# TMC2160.net
KiCad netlist of a schematic drawn in Altium Designer
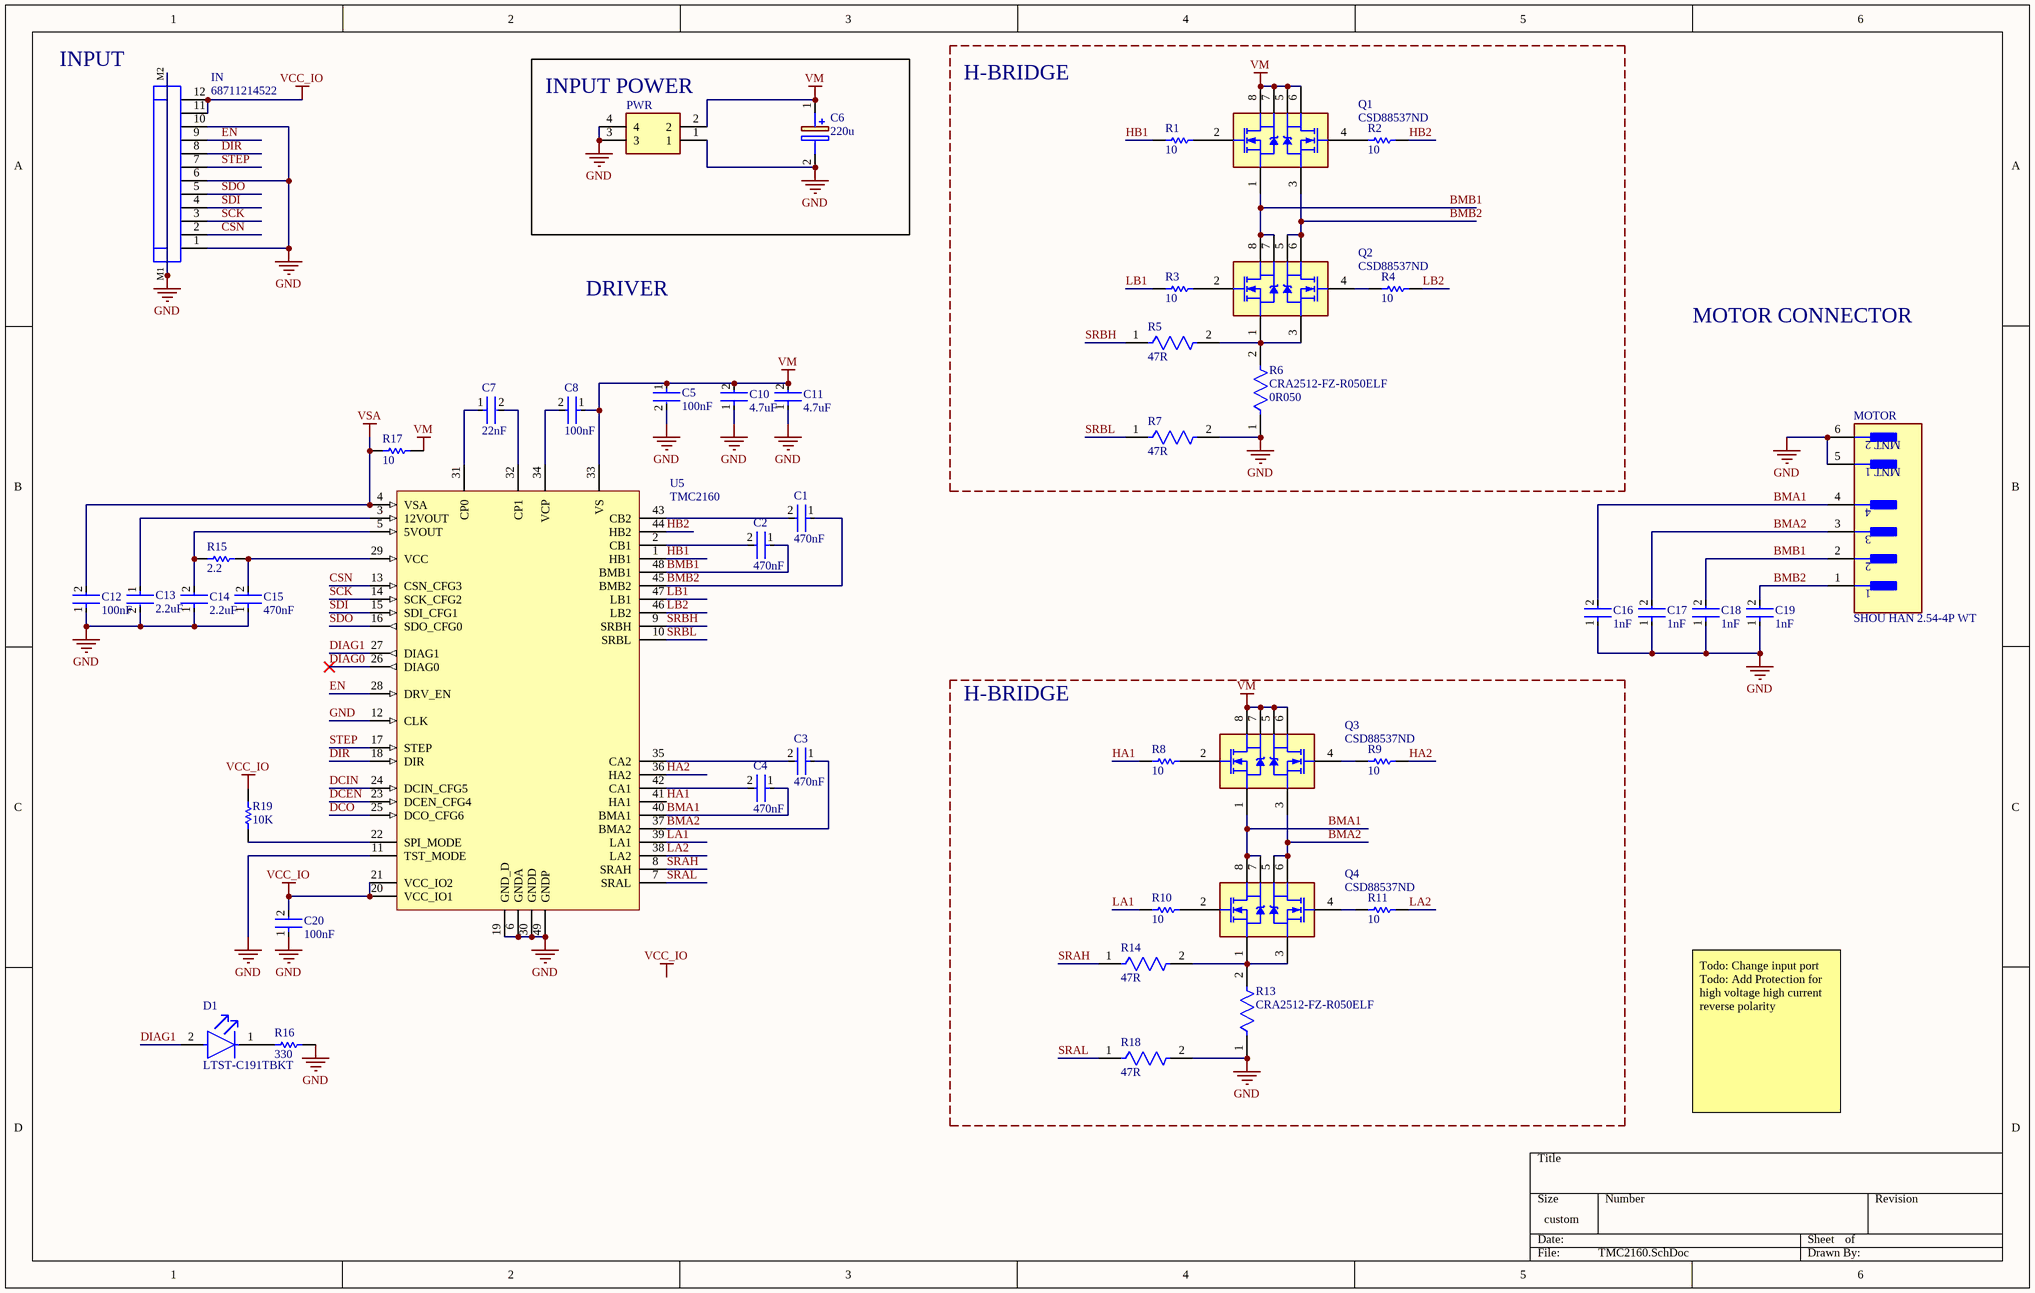
[diagram p0: TMC2160.SchDoc]

(export (version "E")
  (design (tool "Eeschema 10.0.6"))
  (components
    (comp (ref "C1")
      (value "470nF")
      (footprint "FP-C1005-050-0_05-IPC_B")
      (description "Multilayer Ceramic Capacitors 470nF ±10% 35V X5R SMD 0402")
      (fields (field (name "TOLERANCE") "10%") (field (name "Comment") "C1005X5R1V474K050BC"))
      (libsource (lib "Altium Content Vault") (part "b4654b650e69147ec39a6b967a45e02"))
    )
    (comp (ref "C2")
      (value "470nF")
      (footprint "FP-C1005-050-0_05-IPC_B")
      (description "Multilayer Ceramic Capacitors 470nF ±10% 35V X5R SMD 0402")
      (fields (field (name "TOLERANCE") "10%") (field (name "Comment") "C1005X5R1V474K050BC"))
      (libsource (lib "Altium Content Vault") (part "b4654b650e69147ec39a6b967a45e02"))
    )
    (comp (ref "C3")
      (value "470nF")
      (footprint "FP-C1005-050-0_05-IPC_B")
      (description "Multilayer Ceramic Capacitors 470nF ±10% 35V X5R SMD 0402")
      (fields (field (name "TOLERANCE") "10%") (field (name "Comment") "C1005X5R1V474K050BC"))
      (libsource (lib "Altium Content Vault") (part "b4654b650e69147ec39a6b967a45e02"))
    )
    (comp (ref "C4")
      (value "470nF")
      (footprint "FP-C1005-050-0_05-IPC_B")
      (description "Multilayer Ceramic Capacitors 470nF ±10% 35V X5R SMD 0402")
      (fields (field (name "TOLERANCE") "10%") (field (name "Comment") "C1005X5R1V474K050BC"))
      (libsource (lib "Altium Content Vault") (part "b4654b650e69147ec39a6b967a45e02"))
    )
    (comp (ref "C5")
      (value "100nF")
      (footprint "FP-C1005-050-0_05-IPC_C")
      (description "Multilayer Ceramic Capacitors 100nF ±10% 50V X7R SMD 0402")
      (fields (field (name "VOLTAGE") "50V") (field (name "TOLERANCE") "10%"))
      (libsource (lib "Altium Content Vault") (part "b4654b650e69147ec39a6b967a45e02"))
    )
    (comp (ref "C6")
      (value "220u")
      (footprint "SamacSys:CAPAE1030X1050N")
      (description "Capacitor Polarised")
      (fields (field (name "MANUFACTURER_PART_NUMBER") "VZH221M1HTR-1010L"))
      (libsource (lib "SamacSys") (part "VZH221M1HTR-1010L"))
    )
    (comp (ref "C7")
      (value "22nF")
      (footprint "FP-C1005-050-0_05-IPC_C")
      (description "Multilayer Ceramic Capacitors 22nF ±10% 50V X7R SMD 0402")
      (fields (field (name "TOLERANCE") "10%") (field (name "Comment") "C1005X7R1H223K050BB"))
      (libsource (lib "Altium Content Vault") (part "b4654b650e69147ec39a6b967a45e02"))
    )
    (comp (ref "C8")
      (value "100nF")
      (footprint "FP-C1005-050-0_05-IPC_C")
      (description "Multilayer Ceramic Capacitors 100nF ±10% 50V X7R SMD 0402")
      (fields (field (name "VOLTAGE") "50V") (field (name "TOLERANCE") "10%"))
      (libsource (lib "Altium Content Vault") (part "b4654b650e69147ec39a6b967a45e02"))
    )
    (comp (ref "C10")
      (value "4.7uF")
      (footprint "FP-GRM21B-0_15-IPC_B")
      (description "Chip Multilayer Ceramic Capacitors for General Purpose, 0805, 4.7uF, X5R, 15%, 10%, 50V")
      (fields (field (name "TOLERANCE") "10%") (field (name "Comment") "GRM21BR61H475KE51L"))
      (libsource (lib "Altium Content Vault") (part "b4654b650e69147ec39a6b967a45e02"))
    )
    (comp (ref "C11")
      (value "4.7uF")
      (footprint "FP-GRM21B-0_15-IPC_B")
      (description "Chip Multilayer Ceramic Capacitors for General Purpose, 0805, 4.7uF, X5R, 15%, 10%, 50V")
      (fields (field (name "TOLERANCE") "10%") (field (name "Comment") "GRM21BR61H475KE51L"))
      (libsource (lib "Altium Content Vault") (part "b4654b650e69147ec39a6b967a45e02"))
    )
    (comp (ref "C12")
      (value "100nF")
      (footprint "FP-C1005-050-0_05-IPC_C")
      (description "Multilayer Ceramic Capacitors 100nF ±10% 50V X7R SMD 0402")
      (fields (field (name "VOLTAGE") "50V") (field (name "TOLERANCE") "10%"))
      (libsource (lib "Altium Content Vault") (part "b4654b650e69147ec39a6b967a45e02"))
    )
    (comp (ref "C13")
      (value "2.2uF")
      (footprint "FP-C1005-050-0_15-IPC_C")
      (description "CAP CER 2.2UF 35V X5R 0402")
      (fields (field (name "TOLERANCE") "10%") (field (name "Comment") "C1005X5R1V225K050BC"))
      (libsource (lib "Altium Content Vault") (part "11868f565c42a9108669ba33697ecf6"))
    )
    (comp (ref "C14")
      (value "2.2uF")
      (footprint "FP-C1005-050-0_15-IPC_A")
      (description "CAP CER 2.2UF 35V X5R 0402")
      (fields (field (name "TOLERANCE") "10%") (field (name "Comment") "C1005X5R1V225K050BC"))
      (libsource (lib "Altium Content Vault") (part "11868f565c42a9108669ba33697ecf6"))
    )
    (comp (ref "C15")
      (value "470nF")
      (footprint "FP-C1005-050-0_05-IPC_B")
      (description "Multilayer Ceramic Capacitors 470nF ±10% 35V X5R SMD 0402")
      (fields (field (name "TOLERANCE") "10%") (field (name "Comment") "C1005X5R1V474K050BC"))
      (libsource (lib "Altium Content Vault") (part "b4654b650e69147ec39a6b967a45e02"))
    )
    (comp (ref "C16")
      (value "1nF")
      (footprint "FP-C1005-050-0_05-IPC_A")
      (description "Multilayer Ceramic Capacitors 1nF ±10% 50V X7R SMD 0402")
      (fields (field (name "TOLERANCE") "10%") (field (name "VOLTAGE") "50V"))
      (libsource (lib "Altium Content Vault") (part "b4654b650e69147ec39a6b967a45e02"))
    )
    (comp (ref "C17")
      (value "1nF")
      (footprint "FP-C1005-050-0_05-IPC_A")
      (description "Multilayer Ceramic Capacitors 1nF ±10% 50V X7R SMD 0402")
      (fields (field (name "TOLERANCE") "10%") (field (name "VOLTAGE") "50V"))
      (libsource (lib "Altium Content Vault") (part "b4654b650e69147ec39a6b967a45e02"))
    )
    (comp (ref "C18")
      (value "1nF")
      (footprint "FP-C1005-050-0_05-IPC_A")
      (description "Multilayer Ceramic Capacitors 1nF ±10% 50V X7R SMD 0402")
      (fields (field (name "TOLERANCE") "10%") (field (name "VOLTAGE") "50V"))
      (libsource (lib "Altium Content Vault") (part "b4654b650e69147ec39a6b967a45e02"))
    )
    (comp (ref "C19")
      (value "1nF")
      (footprint "FP-C1005-050-0_05-IPC_A")
      (description "Multilayer Ceramic Capacitors 1nF ±10% 50V X7R SMD 0402")
      (fields (field (name "TOLERANCE") "10%") (field (name "VOLTAGE") "50V"))
      (libsource (lib "Altium Content Vault") (part "b4654b650e69147ec39a6b967a45e02"))
    )
    (comp (ref "C20")
      (value "100nF")
      (footprint "FP-C1005-050-0_05-IPC_C")
      (description "Multilayer Ceramic Capacitors 100nF ±10% 50V X7R SMD 0402")
      (fields (field (name "VOLTAGE") "50V") (field (name "TOLERANCE") "10%"))
      (libsource (lib "Altium Content Vault") (part "b4654b650e69147ec39a6b967a45e02"))
    )
    (comp (ref "D1")
      (value "LTST-C191TBKT")
      (footprint "FP-LTST-C191TBKT-MFG")
      (description "LED BLUE CLEAR CHIP SMD")
      (libsource (lib "Altium Content Vault") (part "8706943c75ba83719d021d2fdc84c58"))
    )
    (comp (ref "IN")
      (value "68711214522")
      (footprint "68711214522")
      (libsource (lib "Altium Content Vault") (part "FPC - 12P - 2MP"))
    )
    (comp (ref "MOTOR")
      (value "SHOU HAN 2.54-4P WT")
      (footprint "A2501WF-04A")
      (description "CONN HEADER SMD R/A 4POS 2.5MM")
      (libsource (lib "ParsaLibrary") (part "a9f55b2ccc20dccd0fcbea9c396e26a"))
    )
    (comp (ref "PWR")
      (value "SHOU HAN 2.54-2P WT")
      (footprint "A2501WF-02A")
      (description "Connector")
      (fields
        (field (name "MANUFACTURER_PART_NUMBER") "1778764")
        (field (name "MOUSER PART NUMBER") "651-1778764")
      )
      (libsource (lib "*") (part "1778764"))
    )
    (comp (ref "Q1")
      (value "CSD88537ND")
      (footprint "SamacSys:SOIC127P600X175-8N")
      (description "MOSFET (N-Channel)")
      (fields (field (name "MOUSER PART NUMBER") "595-CSD88537ND"))
      (libsource (lib "SamacSys") (part "CSD88537ND"))
    )
    (comp (ref "Q2")
      (value "CSD88537ND")
      (footprint "SamacSys:SOIC127P600X175-8N")
      (description "MOSFET (N-Channel)")
      (fields (field (name "MOUSER PART NUMBER") "595-CSD88537ND"))
      (libsource (lib "SamacSys") (part "CSD88537ND"))
    )
    (comp (ref "Q3")
      (value "CSD88537ND")
      (footprint "SamacSys:SOIC127P600X175-8N")
      (description "MOSFET (N-Channel)")
      (fields (field (name "MOUSER PART NUMBER") "595-CSD88537ND"))
      (libsource (lib "SamacSys") (part "CSD88537ND"))
    )
    (comp (ref "Q4")
      (value "CSD88537ND")
      (footprint "SamacSys:SOIC127P600X175-8N")
      (description "MOSFET (N-Channel)")
      (fields (field (name "MOUSER PART NUMBER") "595-CSD88537ND"))
      (libsource (lib "SamacSys") (part "CSD88537ND"))
    )
    (comp (ref "R1")
      (value "10")
      (footprint "RESC1005X40X25ML05T10")
      (fields
        (field (name "PART NUMBER") "RC0402FR-07100RL")
        (field (name "MANUFACTURER") "Yageo / Phycomp")
        (field (name "Comment") "RC0402FR-0710RL")
      )
      (libsource (lib "Altium Content Vault") (part "RES"))
    )
    (comp (ref "R2")
      (value "10")
      (footprint "RESC1005X40X25ML05T10")
      (fields
        (field (name "PART NUMBER") "RC0402FR-07100RL")
        (field (name "MANUFACTURER") "Yageo / Phycomp")
        (field (name "Comment") "RC0402FR-0710RL")
      )
      (libsource (lib "Altium Content Vault") (part "RES"))
    )
    (comp (ref "R3")
      (value "10")
      (footprint "RESC1005X40X25ML05T10")
      (fields
        (field (name "PART NUMBER") "RC0402FR-07100RL")
        (field (name "MANUFACTURER") "Yageo / Phycomp")
        (field (name "Comment") "RC0402FR-0710RL")
      )
      (libsource (lib "Altium Content Vault") (part "RES"))
    )
    (comp (ref "R4")
      (value "10")
      (footprint "RESC1005X40X25ML05T10")
      (fields
        (field (name "PART NUMBER") "RC0402FR-07100RL")
        (field (name "MANUFACTURER") "Yageo / Phycomp")
        (field (name "Comment") "RC0402FR-0710RL")
      )
      (libsource (lib "Altium Content Vault") (part "RES"))
    )
    (comp (ref "R5")
      (value "47R")
      (footprint "FP-ERJ2RK-IPC_C")
      (description "RES SMD 47 OHM 1% 1/10W 0402")
      (fields (field (name "TOLERANCE") "1%") (field (name "Comment") "ERJ-2RKF47R0X"))
      (libsource (lib "Altium Content Vault") (part "1029c3af85768c4190bb7ad29bc67b5"))
    )
    (comp (ref "R6")
      (value "CRA2512-FZ-R050ELF")
      (footprint "FP-CRA2512-IPC_A")
      (description "RES 0.05 OHM 1% 3W 2512")
      (fields (field (name "ALTIUM_VALUE") "0R050"))
      (libsource (lib "Altium Content Vault") (part "1029c3af85768c4190bb7ad29bc67b5"))
    )
    (comp (ref "R7")
      (value "47R")
      (footprint "FP-ERJ2RK-IPC_C")
      (description "RES SMD 47 OHM 1% 1/10W 0402")
      (fields (field (name "TOLERANCE") "1%") (field (name "Comment") "ERJ-2RKF47R0X"))
      (libsource (lib "Altium Content Vault") (part "1029c3af85768c4190bb7ad29bc67b5"))
    )
    (comp (ref "R8")
      (value "10")
      (footprint "RESC1005X40X25ML05T10")
      (fields
        (field (name "PART NUMBER") "RC0402FR-07100RL")
        (field (name "MANUFACTURER") "Yageo / Phycomp")
        (field (name "Comment") "RC0402FR-0710RL")
      )
      (libsource (lib "Altium Content Vault") (part "RES"))
    )
    (comp (ref "R9")
      (value "10")
      (footprint "RESC1005X40X25ML05T10")
      (fields
        (field (name "PART NUMBER") "RC0402FR-07100RL")
        (field (name "MANUFACTURER") "Yageo / Phycomp")
        (field (name "Comment") "RC0402FR-0710RL")
      )
      (libsource (lib "Altium Content Vault") (part "RES"))
    )
    (comp (ref "R10")
      (value "10")
      (footprint "RESC1005X40X25ML05T10")
      (fields
        (field (name "PART NUMBER") "RC0402FR-07100RL")
        (field (name "MANUFACTURER") "Yageo / Phycomp")
        (field (name "Comment") "RC0402FR-0710RL")
      )
      (libsource (lib "Altium Content Vault") (part "RES"))
    )
    (comp (ref "R11")
      (value "10")
      (footprint "RESC1005X40X25ML05T10")
      (fields
        (field (name "PART NUMBER") "RC0402FR-07100RL")
        (field (name "MANUFACTURER") "Yageo / Phycomp")
        (field (name "Comment") "RC0402FR-0710RL")
      )
      (libsource (lib "Altium Content Vault") (part "RES"))
    )
    (comp (ref "R13")
      (value "CRA2512-FZ-R050ELF")
      (footprint "FP-CRA2512-IPC_A")
      (description "RES 0.05 OHM 1% 3W 2512")
      (libsource (lib "Altium Content Vault") (part "1029c3af85768c4190bb7ad29bc67b5"))
    )
    (comp (ref "R14")
      (value "47R")
      (footprint "FP-ERJ2RK-IPC_C")
      (description "RES SMD 47 OHM 1% 1/10W 0402")
      (fields (field (name "TOLERANCE") "1%") (field (name "Comment") "ERJ-2RKF47R0X"))
      (libsource (lib "Altium Content Vault") (part "1029c3af85768c4190bb7ad29bc67b5"))
    )
    (comp (ref "R15")
      (value "ERJ-2GEJ2R2X")
      (footprint "RESC1005X40X25ML05T05")
      (fields (field (name "MANUFACTURER") "Panasonic") (field (name "RESISTANCE") "2.2"))
      (libsource (lib "Altium Content Vault") (part "RES"))
    )
    (comp (ref "R16")
      (value "330")
      (footprint "RESC1005X40X25LL05T10")
      (fields (field (name "PART NUMBER") "RC0402FR-07330RL") (field (name "MANUFACTURER") "Yageo / Phycomp"))
      (libsource (lib "Altium Content Vault") (part "RES"))
    )
    (comp (ref "R17")
      (value "10")
      (footprint "RESC1005X40X25ML05T10")
      (fields
        (field (name "PART NUMBER") "RC0402FR-07100RL")
        (field (name "MANUFACTURER") "Yageo / Phycomp")
        (field (name "Comment") "RC0402FR-0710RL")
      )
      (libsource (lib "Altium Content Vault") (part "RES"))
    )
    (comp (ref "R18")
      (value "47R")
      (footprint "FP-ERJ2RK-IPC_C")
      (description "RES SMD 47 OHM 1% 1/10W 0402")
      (fields (field (name "TOLERANCE") "1%") (field (name "Comment") "ERJ-2RKF47R0X"))
      (libsource (lib "Altium Content Vault") (part "1029c3af85768c4190bb7ad29bc67b5"))
    )
    (comp (ref "R19")
      (value "10K")
      (footprint "RESC1005X40X25LL05T10")
      (fields (field (name "PART NUMBER") "RC0402FR-0710KL") (field (name "MANUFACTURER") "Yageo / Phycomp"))
      (libsource (lib "Altium Content Vault") (part "RES"))
    )
    (comp (ref "U5") (value "TMC2160") (footprint "TSQFP-48") (libsource (lib "Schlib2") (part "TMC2160")))
  )
  (nets
    (net (code "1") (name "/BMA1") (class "Default")
      (node (ref "C16") (pin "2") (pinfunction "2_2") (pintype "passive"))
      (node (ref "C4") (pin "1") (pinfunction "1_1") (pintype "passive"))
      (node (ref "MOTOR") (pin "4") (pinfunction "4_4") (pintype "passive"))
      (node (ref "Q3") (pin "1") (pinfunction "S1_1") (pintype "passive"))
      (node (ref "Q4") (pin "7") (pinfunction "D1_1_7") (pintype "passive"))
      (node (ref "Q4") (pin "8") (pinfunction "D1_2_8") (pintype "passive"))
      (node (ref "U5") (pin "40") (pinfunction "BMA1_40") (pintype "passive"))
    )
    (net (code "2") (name "/BMA2") (class "Default")
      (node (ref "C17") (pin "2") (pinfunction "2_2") (pintype "passive"))
      (node (ref "C3") (pin "1") (pinfunction "1_1") (pintype "passive"))
      (node (ref "MOTOR") (pin "3") (pinfunction "3_3") (pintype "passive"))
      (node (ref "Q3") (pin "3") (pinfunction "S2_3") (pintype "passive"))
      (node (ref "Q4") (pin "5") (pinfunction "D2_1_5") (pintype "passive"))
      (node (ref "Q4") (pin "6") (pinfunction "D2_2_6") (pintype "passive"))
      (node (ref "U5") (pin "37") (pinfunction "BMA2_37") (pintype "passive"))
    )
    (net (code "3") (name "/BMB1") (class "Default")
      (node (ref "C18") (pin "2") (pinfunction "2_2") (pintype "passive"))
      (node (ref "C2") (pin "1") (pinfunction "1_1") (pintype "passive"))
      (node (ref "MOTOR") (pin "2") (pinfunction "2_2") (pintype "passive"))
      (node (ref "Q1") (pin "1") (pinfunction "S1_1") (pintype "passive"))
      (node (ref "Q2") (pin "7") (pinfunction "D1_1_7") (pintype "passive"))
      (node (ref "Q2") (pin "8") (pinfunction "D1_2_8") (pintype "passive"))
      (node (ref "U5") (pin "48") (pinfunction "BMB1_48") (pintype "passive"))
    )
    (net (code "4") (name "/BMB2") (class "Default")
      (node (ref "C1") (pin "1") (pinfunction "1_1") (pintype "passive"))
      (node (ref "C19") (pin "2") (pinfunction "2_2") (pintype "passive"))
      (node (ref "MOTOR") (pin "1") (pinfunction "1_1") (pintype "passive"))
      (node (ref "Q1") (pin "3") (pinfunction "S2_3") (pintype "passive"))
      (node (ref "Q2") (pin "5") (pinfunction "D2_1_5") (pintype "passive"))
      (node (ref "Q2") (pin "6") (pinfunction "D2_2_6") (pintype "passive"))
      (node (ref "U5") (pin "45") (pinfunction "BMB2_45") (pintype "passive"))
    )
    (net (code "5") (name "/CSN") (class "Default")
      (node (ref "IN") (pin "2") (pinfunction "2_2") (pintype "passive"))
      (node (ref "U5") (pin "13") (pinfunction "CSN_CFG3_13") (pintype "input"))
    )
    (net (code "6") (name "/DCEN") (class "Default")
      (node (ref "U5") (pin "23") (pinfunction "DCEN_CFG4_23") (pintype "input"))
    )
    (net (code "7") (name "/DCIN") (class "Default")
      (node (ref "U5") (pin "24") (pinfunction "DCIN_CFG5_24") (pintype "input"))
    )
    (net (code "8") (name "/DCO") (class "Default")
      (node (ref "U5") (pin "25") (pinfunction "DCO_CFG6_25") (pintype "input"))
    )
    (net (code "9") (name "/DIAG0") (class "Default")
      (node (ref "U5") (pin "26") (pinfunction "DIAG0_26") (pintype "output+no_connect"))
    )
    (net (code "10") (name "/DIAG1") (class "Default")
      (node (ref "D1") (pin "2") (pinfunction "A_2") (pintype "passive"))
      (node (ref "U5") (pin "27") (pinfunction "DIAG1_27") (pintype "output"))
    )
    (net (code "11") (name "/DIR") (class "Default")
      (node (ref "IN") (pin "8") (pinfunction "8_8") (pintype "passive"))
      (node (ref "U5") (pin "18") (pinfunction "DIR_18") (pintype "input"))
    )
    (net (code "12") (name "/EN") (class "Default")
      (node (ref "IN") (pin "9") (pinfunction "9_9") (pintype "passive"))
      (node (ref "U5") (pin "28") (pinfunction "DRV_EN_28") (pintype "input"))
    )
    (net (code "13") (name "/HA1") (class "Default")
      (node (ref "R8") (pin "2") (pinfunction "2_2") (pintype "passive"))
      (node (ref "U5") (pin "41") (pinfunction "HA1_41") (pintype "passive"))
    )
    (net (code "14") (name "/HA2") (class "Default")
      (node (ref "R9") (pin "1") (pinfunction "1_1") (pintype "passive"))
      (node (ref "U5") (pin "36") (pinfunction "HA2_36") (pintype "passive"))
    )
    (net (code "15") (name "/HB1") (class "Default")
      (node (ref "R1") (pin "2") (pinfunction "2_2") (pintype "passive"))
      (node (ref "U5") (pin "1") (pinfunction "HB1_1") (pintype "passive"))
    )
    (net (code "16") (name "/HB2") (class "Default")
      (node (ref "R2") (pin "1") (pinfunction "1_1") (pintype "passive"))
      (node (ref "U5") (pin "44") (pinfunction "HB2_44") (pintype "passive"))
    )
    (net (code "17") (name "/LA1") (class "Default")
      (node (ref "R10") (pin "2") (pinfunction "2_2") (pintype "passive"))
      (node (ref "U5") (pin "39") (pinfunction "LA1_39") (pintype "passive"))
    )
    (net (code "18") (name "/LA2") (class "Default")
      (node (ref "R11") (pin "1") (pinfunction "1_1") (pintype "passive"))
      (node (ref "U5") (pin "38") (pinfunction "LA2_38") (pintype "passive"))
    )
    (net (code "19") (name "/LB1") (class "Default")
      (node (ref "R3") (pin "2") (pinfunction "2_2") (pintype "passive"))
      (node (ref "U5") (pin "47") (pinfunction "LB1_47") (pintype "passive"))
    )
    (net (code "20") (name "/LB2") (class "Default")
      (node (ref "R4") (pin "1") (pinfunction "1_1") (pintype "passive"))
      (node (ref "U5") (pin "46") (pinfunction "LB2_46") (pintype "passive"))
    )
    (net (code "21") (name "/SCK") (class "Default")
      (node (ref "IN") (pin "3") (pinfunction "3_3") (pintype "passive"))
      (node (ref "U5") (pin "14") (pinfunction "SCK_CFG2_14") (pintype "input"))
    )
    (net (code "22") (name "/SDI") (class "Default")
      (node (ref "IN") (pin "4") (pinfunction "4_4") (pintype "passive"))
      (node (ref "U5") (pin "15") (pinfunction "SDI_CFG1_15") (pintype "input"))
    )
    (net (code "23") (name "/SDO") (class "Default")
      (node (ref "IN") (pin "5") (pinfunction "5_5") (pintype "passive"))
      (node (ref "U5") (pin "16") (pinfunction "SDO_CFG0_16") (pintype "output"))
    )
    (net (code "24") (name "/SRAH") (class "Default")
      (node (ref "R14") (pin "1") (pinfunction "1_1") (pintype "passive"))
      (node (ref "U5") (pin "8") (pinfunction "SRAH_8") (pintype "passive"))
    )
    (net (code "25") (name "/SRAL") (class "Default")
      (node (ref "R18") (pin "1") (pinfunction "1_1") (pintype "passive"))
      (node (ref "U5") (pin "7") (pinfunction "SRAL_7") (pintype "passive"))
    )
    (net (code "26") (name "/SRBH") (class "Default")
      (node (ref "R5") (pin "1") (pinfunction "1_1") (pintype "passive"))
      (node (ref "U5") (pin "9") (pinfunction "SRBH_9") (pintype "passive"))
    )
    (net (code "27") (name "/SRBL") (class "Default")
      (node (ref "R7") (pin "1") (pinfunction "1_1") (pintype "passive"))
      (node (ref "U5") (pin "10") (pinfunction "SRBL_10") (pintype "passive"))
    )
    (net (code "28") (name "/STEP") (class "Default")
      (node (ref "IN") (pin "7") (pinfunction "7_7") (pintype "passive"))
      (node (ref "U5") (pin "17") (pinfunction "STEP_17") (pintype "input"))
    )
    (net (code "29") (name "GND") (class "Default")
      (node (ref "C10") (pin "1") (pinfunction "1_1") (pintype "passive"))
      (node (ref "C11") (pin "1") (pinfunction "1_1") (pintype "passive"))
      (node (ref "C12") (pin "1") (pinfunction "1_1") (pintype "passive"))
      (node (ref "C13") (pin "2") (pinfunction "2_2") (pintype "passive"))
      (node (ref "C14") (pin "1") (pinfunction "1_1") (pintype "passive"))
      (node (ref "C15") (pin "1") (pinfunction "1_1") (pintype "passive"))
      (node (ref "C16") (pin "1") (pinfunction "1_1") (pintype "passive"))
      (node (ref "C17") (pin "1") (pinfunction "1_1") (pintype "passive"))
      (node (ref "C18") (pin "1") (pinfunction "1_1") (pintype "passive"))
      (node (ref "C19") (pin "1") (pinfunction "1_1") (pintype "passive"))
      (node (ref "C20") (pin "1") (pinfunction "1_1") (pintype "passive"))
      (node (ref "C5") (pin "2") (pinfunction "2_2") (pintype "passive"))
      (node (ref "C6") (pin "2") (pinfunction "-_2") (pintype "passive"))
      (node (ref "IN") (pin "1") (pinfunction "1_1") (pintype "passive"))
      (node (ref "IN") (pin "10") (pinfunction "10_10") (pintype "passive"))
      (node (ref "IN") (pin "6") (pinfunction "6_6") (pintype "passive"))
      (node (ref "IN") (pin "M1") (pinfunction "M1_M1") (pintype "passive"))
      (node (ref "IN") (pin "M2") (pinfunction "M2_M2") (pintype "passive"))
      (node (ref "MOTOR") (pin "5") (pinfunction "MNT_1_5") (pintype "passive"))
      (node (ref "MOTOR") (pin "6") (pinfunction "MNT_2_6") (pintype "passive"))
      (node (ref "PWR") (pin "1") (pinfunction "1_1") (pintype "passive"))
      (node (ref "PWR") (pin "3") (pinfunction "3_3") (pintype "passive"))
      (node (ref "PWR") (pin "4") (pinfunction "4_4") (pintype "passive"))
      (node (ref "R13") (pin "1") (pinfunction "1_1") (pintype "passive"))
      (node (ref "R16") (pin "1") (pinfunction "1_1") (pintype "passive"))
      (node (ref "R18") (pin "2") (pinfunction "2_2") (pintype "passive"))
      (node (ref "R6") (pin "1") (pinfunction "1_1") (pintype "passive"))
      (node (ref "R7") (pin "2") (pinfunction "2_2") (pintype "passive"))
      (node (ref "U5") (pin "11") (pinfunction "TST_MODE_11") (pintype "passive"))
      (node (ref "U5") (pin "12") (pinfunction "CLK_12") (pintype "input"))
      (node (ref "U5") (pin "19") (pinfunction "GND_D_19") (pintype "power_in"))
      (node (ref "U5") (pin "30") (pinfunction "GNDD_30") (pintype "power_in"))
      (node (ref "U5") (pin "49") (pinfunction "GNDP_49") (pintype "power_in"))
      (node (ref "U5") (pin "6") (pinfunction "GNDA_6") (pintype "power_in"))
    )
    (net (code "30") (name "Net-(D1-C)") (class "Default")
      (node (ref "D1") (pin "1") (pinfunction "C_1") (pintype "passive"))
      (node (ref "R16") (pin "2") (pinfunction "2_2") (pintype "passive"))
    )
    (net (code "31") (name "Net-(Q1-G1)") (class "Default")
      (node (ref "Q1") (pin "2") (pinfunction "G1_2") (pintype "passive"))
      (node (ref "R1") (pin "1") (pinfunction "1_1") (pintype "passive"))
    )
    (net (code "32") (name "Net-(Q1-G2)") (class "Default")
      (node (ref "Q1") (pin "4") (pinfunction "G2_4") (pintype "passive"))
      (node (ref "R2") (pin "2") (pinfunction "2_2") (pintype "passive"))
    )
    (net (code "33") (name "Net-(Q2-G1)") (class "Default")
      (node (ref "Q2") (pin "2") (pinfunction "G1_2") (pintype "passive"))
      (node (ref "R3") (pin "1") (pinfunction "1_1") (pintype "passive"))
    )
    (net (code "34") (name "Net-(Q2-G2)") (class "Default")
      (node (ref "Q2") (pin "4") (pinfunction "G2_4") (pintype "passive"))
      (node (ref "R4") (pin "2") (pinfunction "2_2") (pintype "passive"))
    )
    (net (code "35") (name "Net-(Q2-S1)") (class "Default")
      (node (ref "Q2") (pin "1") (pinfunction "S1_1") (pintype "passive"))
      (node (ref "Q2") (pin "3") (pinfunction "S2_3") (pintype "passive"))
      (node (ref "R5") (pin "2") (pinfunction "2_2") (pintype "passive"))
      (node (ref "R6") (pin "2") (pinfunction "2_2") (pintype "passive"))
    )
    (net (code "36") (name "Net-(Q3-G1)") (class "Default")
      (node (ref "Q3") (pin "2") (pinfunction "G1_2") (pintype "passive"))
      (node (ref "R8") (pin "1") (pinfunction "1_1") (pintype "passive"))
    )
    (net (code "37") (name "Net-(Q3-G2)") (class "Default")
      (node (ref "Q3") (pin "4") (pinfunction "G2_4") (pintype "passive"))
      (node (ref "R9") (pin "2") (pinfunction "2_2") (pintype "passive"))
    )
    (net (code "38") (name "Net-(Q4-G1)") (class "Default")
      (node (ref "Q4") (pin "2") (pinfunction "G1_2") (pintype "passive"))
      (node (ref "R10") (pin "1") (pinfunction "1_1") (pintype "passive"))
    )
    (net (code "39") (name "Net-(Q4-G2)") (class "Default")
      (node (ref "Q4") (pin "4") (pinfunction "G2_4") (pintype "passive"))
      (node (ref "R11") (pin "2") (pinfunction "2_2") (pintype "passive"))
    )
    (net (code "40") (name "Net-(Q4-S1)") (class "Default")
      (node (ref "Q4") (pin "1") (pinfunction "S1_1") (pintype "passive"))
      (node (ref "Q4") (pin "3") (pinfunction "S2_3") (pintype "passive"))
      (node (ref "R13") (pin "2") (pinfunction "2_2") (pintype "passive"))
      (node (ref "R14") (pin "2") (pinfunction "2_2") (pintype "passive"))
    )
    (net (code "41") (name "Net-(U5-5VOUT)") (class "Default")
      (node (ref "C14") (pin "2") (pinfunction "2_2") (pintype "passive"))
      (node (ref "R15") (pin "2") (pinfunction "2_2") (pintype "passive"))
      (node (ref "U5") (pin "5") (pinfunction "5VOUT_5") (pintype "input"))
    )
    (net (code "42") (name "Net-(U5-12VOUT)") (class "Default")
      (node (ref "C13") (pin "1") (pinfunction "1_1") (pintype "passive"))
      (node (ref "U5") (pin "3") (pinfunction "12VOUT_3") (pintype "input"))
    )
    (net (code "43") (name "Net-(U5-CA1)") (class "Default")
      (node (ref "C4") (pin "2") (pinfunction "2_2") (pintype "passive"))
      (node (ref "U5") (pin "42") (pinfunction "CA1_42") (pintype "passive"))
    )
    (net (code "44") (name "Net-(U5-CA2)") (class "Default")
      (node (ref "C3") (pin "2") (pinfunction "2_2") (pintype "passive"))
      (node (ref "U5") (pin "35") (pinfunction "CA2_35") (pintype "passive"))
    )
    (net (code "45") (name "Net-(U5-CB1)") (class "Default")
      (node (ref "C2") (pin "2") (pinfunction "2_2") (pintype "passive"))
      (node (ref "U5") (pin "2") (pinfunction "CB1_2") (pintype "passive"))
    )
    (net (code "46") (name "Net-(U5-CB2)") (class "Default")
      (node (ref "C1") (pin "2") (pinfunction "2_2") (pintype "passive"))
      (node (ref "U5") (pin "43") (pinfunction "CB2_43") (pintype "passive"))
    )
    (net (code "47") (name "Net-(U5-CP0)") (class "Default")
      (node (ref "C7") (pin "1") (pinfunction "1_1") (pintype "passive"))
      (node (ref "U5") (pin "31") (pinfunction "CP0_31") (pintype "power_in"))
    )
    (net (code "48") (name "Net-(U5-CP1)") (class "Default")
      (node (ref "C7") (pin "2") (pinfunction "2_2") (pintype "passive"))
      (node (ref "U5") (pin "32") (pinfunction "CP1_32") (pintype "power_in"))
    )
    (net (code "49") (name "Net-(U5-SPI_MODE)") (class "Default")
      (node (ref "R19") (pin "1") (pinfunction "1_1") (pintype "passive"))
      (node (ref "U5") (pin "22") (pinfunction "SPI_MODE_22") (pintype "passive"))
    )
    (net (code "50") (name "Net-(U5-VCC)") (class "Default")
      (node (ref "C15") (pin "2") (pinfunction "2_2") (pintype "passive"))
      (node (ref "R15") (pin "1") (pinfunction "1_1") (pintype "passive"))
      (node (ref "U5") (pin "29") (pinfunction "VCC_29") (pintype "input"))
    )
    (net (code "51") (name "Net-(U5-VCP)") (class "Default")
      (node (ref "C8") (pin "2") (pinfunction "2_2") (pintype "passive"))
      (node (ref "U5") (pin "34") (pinfunction "VCP_34") (pintype "power_in"))
    )
    (net (code "52") (name "VCC_IO") (class "Default")
      (node (ref "C20") (pin "2") (pinfunction "2_2") (pintype "passive"))
      (node (ref "IN") (pin "11") (pinfunction "11_11") (pintype "passive"))
      (node (ref "IN") (pin "12") (pinfunction "12_12") (pintype "passive"))
      (node (ref "R19") (pin "2") (pinfunction "2_2") (pintype "passive"))
      (node (ref "U5") (pin "20") (pinfunction "VCC_IO1_20") (pintype "power_in"))
      (node (ref "U5") (pin "21") (pinfunction "VCC_IO2_21") (pintype "power_in"))
    )
    (net (code "53") (name "VM") (class "Default")
      (node (ref "C10") (pin "2") (pinfunction "2_2") (pintype "passive"))
      (node (ref "C11") (pin "2") (pinfunction "2_2") (pintype "passive"))
      (node (ref "C5") (pin "1") (pinfunction "1_1") (pintype "passive"))
      (node (ref "C6") (pin "1") (pinfunction "+_1") (pintype "passive"))
      (node (ref "C8") (pin "1") (pinfunction "1_1") (pintype "passive"))
      (node (ref "PWR") (pin "2") (pinfunction "2_2") (pintype "passive"))
      (node (ref "Q1") (pin "5") (pinfunction "D2_1_5") (pintype "passive"))
      (node (ref "Q1") (pin "6") (pinfunction "D2_2_6") (pintype "passive"))
      (node (ref "Q1") (pin "7") (pinfunction "D1_1_7") (pintype "passive"))
      (node (ref "Q1") (pin "8") (pinfunction "D1_2_8") (pintype "passive"))
      (node (ref "Q3") (pin "5") (pinfunction "D2_1_5") (pintype "passive"))
      (node (ref "Q3") (pin "6") (pinfunction "D2_2_6") (pintype "passive"))
      (node (ref "Q3") (pin "7") (pinfunction "D1_1_7") (pintype "passive"))
      (node (ref "Q3") (pin "8") (pinfunction "D1_2_8") (pintype "passive"))
      (node (ref "R17") (pin "1") (pinfunction "1_1") (pintype "passive"))
      (node (ref "U5") (pin "33") (pinfunction "VS_33") (pintype "power_in"))
    )
    (net (code "54") (name "VSA") (class "Default")
      (node (ref "C12") (pin "2") (pinfunction "2_2") (pintype "passive"))
      (node (ref "R17") (pin "2") (pinfunction "2_2") (pintype "passive"))
      (node (ref "U5") (pin "4") (pinfunction "VSA_4") (pintype "input"))
    )
  )
)
